# Schematic_1_0.net
KiCad netlist of a schematic drawn in Altium Designer
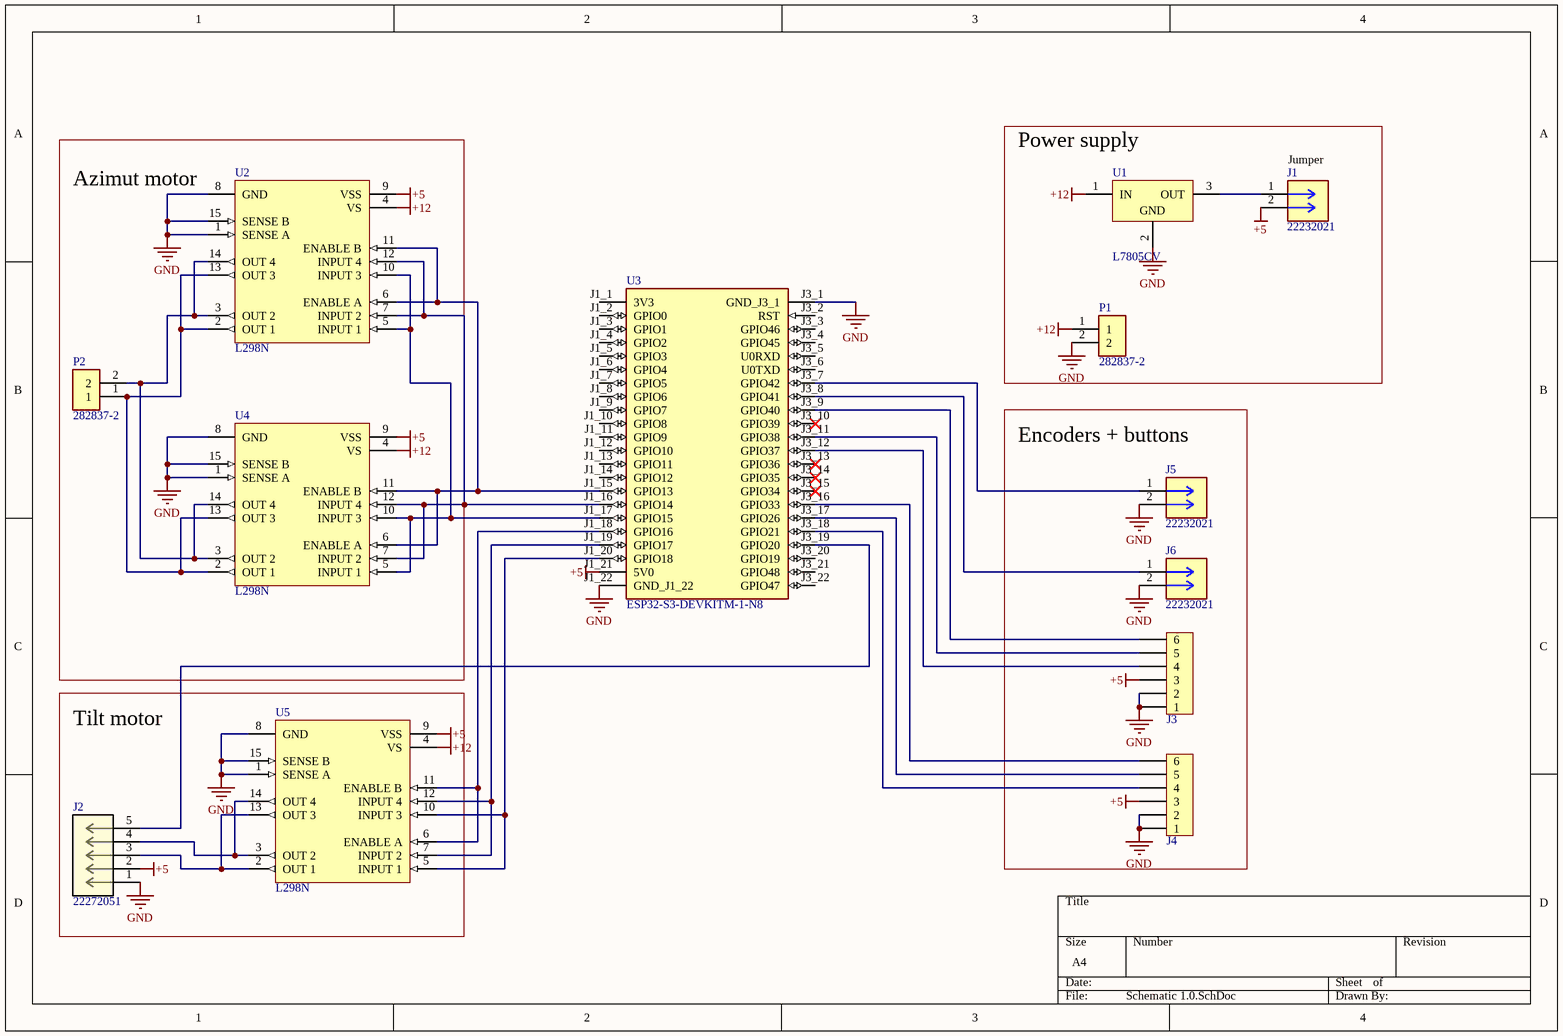
[diagram p0: Schematic 1.0.SchDoc]

(export (version "E")
  (design (tool "Eeschema 10.0.6"))
  (components
    (comp (ref "J1")
      (value "22232021")
      (footprint "CONN_A-6373-02A_MOL")
      (description "Connector Header Through Hole 2 position 0.100 (2.54mm)")
      (fields (field (name "MF") "Molex"))
      (libsource (lib "Emil Beier") (part "22232021"))
    )
    (comp (ref "J2")
      (value "22272051")
      (footprint "CONN_AE-6410-05A_MOL")
      (description "KK 254 Wire-to-Board Header, Vertical, with Friction Lock, 5 Circuits, Tin (Sn) Plating")
      (fields (field (name "COPYRIGHT") "Copyright (C) 2025 Ultra Librarian. All rights reserved."))
      (libsource (lib "22272051 - 5pin molex") (part "22272051"))
    )
    (comp (ref "J3")
      (value "Header 1x6")
      (footprint "Header 1x6")
      (libsource (lib "AAURacing") (part "Header 1x6"))
    )
    (comp (ref "J4")
      (value "Header 1x6")
      (footprint "Header 1x6")
      (libsource (lib "AAURacing") (part "Header 1x6"))
    )
    (comp (ref "J5")
      (value "22232021")
      (footprint "CONN_A-6373-02A_MOL")
      (description "Connector Header Through Hole 2 position 0.100 (2.54mm)")
      (fields (field (name "MF") "Molex"))
      (libsource (lib "Emil Beier") (part "22232021"))
    )
    (comp (ref "J6")
      (value "22232021")
      (footprint "CONN_A-6373-02A_MOL")
      (description "Connector Header Through Hole 2 position 0.100 (2.54mm)")
      (fields (field (name "MF") "Molex"))
      (libsource (lib "Emil Beier") (part "22232021"))
    )
    (comp (ref "P1")
      (value "282837-2")
      (footprint "TE_282837-2")
      (fields (field (name "MF") "TE Connectivity"))
      (libsource (lib "Emil Beier") (part "282837-2"))
    )
    (comp (ref "P2")
      (value "282837-2")
      (footprint "TE_282837-2")
      (fields (field (name "MF") "TE Connectivity"))
      (libsource (lib "") (part "282837-2_1"))
    )
    (comp (ref "U1")
      (value "L7805CV")
      (footprint "TO220")
      (description "Positive Voltage Regulator, 5V, 3-Pin TO-220")
      (libsource (lib "Altium Content Vault") (part "PM-REG-L4940-SIL3"))
    )
    (comp (ref "U2")
      (value "L298N")
      (footprint "STM-FM-15")
      (description "Dual Full-Bridge Driver, 4.8 to 46 V, -40 to 150 degC, 15-Pin FM (MW 15L), RoHS, Tube")
      (fields (field (name "MANUFACTURER") "STMicroelectronics") (field (name "PARTNUMBER") "L298"))
      (libsource (lib "Altium Content Vault") (part "STM-L298-15"))
    )
    (comp (ref "U3")
      (value "ESP32-S3-DEVKITM-1-N8")
      (footprint "MODULE_ESP32-S3-DEVKITM-1-N8")
      (fields (field (name "MF") "{'manufacturer': u'Espressif Systems'}"))
      (libsource (lib "Emil Beier") (part "ESP32-S3-DEVKITM-1-N8"))
    )
    (comp (ref "U4")
      (value "L298N")
      (footprint "STM-FM-15")
      (description "Dual Full-Bridge Driver, 4.8 to 46 V, -40 to 150 degC, 15-Pin FM (MW 15L), RoHS, Tube")
      (fields (field (name "MANUFACTURER") "STMicroelectronics") (field (name "PARTNUMBER") "L298"))
      (libsource (lib "Altium Content Vault") (part "STM-L298-15"))
    )
    (comp (ref "U5")
      (value "L298N")
      (footprint "STM-FM-15")
      (description "Dual Full-Bridge Driver, 4.8 to 46 V, -40 to 150 degC, 15-Pin FM (MW 15L), RoHS, Tube")
      (fields (field (name "MANUFACTURER") "STMicroelectronics") (field (name "PARTNUMBER") "L298"))
      (libsource (lib "Altium Content Vault") (part "STM-L298-15"))
    )
  )
  (nets
    (net (code "1") (name "+5") (class "Default")
      (node (ref "J1") (pin "2") (pinfunction "2_2") (pintype "passive"))
      (node (ref "J2") (pin "2") (pinfunction "2_2") (pintype "passive"))
      (node (ref "J3") (pin "3") (pinfunction "3_3") (pintype "passive"))
      (node (ref "J4") (pin "3") (pinfunction "3_3") (pintype "passive"))
      (node (ref "U2") (pin "9") (pinfunction "VSS_9") (pintype "power_in"))
      (node (ref "U3") (pin "J1_21") (pinfunction "5V0_J1_21") (pintype "power_in"))
      (node (ref "U4") (pin "9") (pinfunction "VSS_9") (pintype "power_in"))
      (node (ref "U5") (pin "9") (pinfunction "VSS_9") (pintype "power_in"))
    )
    (net (code "2") (name "+12") (class "Default")
      (node (ref "P1") (pin "1") (pinfunction "1_1") (pintype "passive"))
      (node (ref "U1") (pin "1") (pinfunction "IN_1") (pintype "power_in"))
      (node (ref "U2") (pin "4") (pinfunction "VS_4") (pintype "power_in"))
      (node (ref "U4") (pin "4") (pinfunction "VS_4") (pintype "power_in"))
      (node (ref "U5") (pin "4") (pinfunction "VS_4") (pintype "power_in"))
    )
    (net (code "3") (name "GND") (class "Default")
      (node (ref "J2") (pin "1") (pinfunction "1_1") (pintype "passive"))
      (node (ref "J3") (pin "1") (pinfunction "1_1") (pintype "passive"))
      (node (ref "J3") (pin "2") (pinfunction "2_2") (pintype "passive"))
      (node (ref "J4") (pin "1") (pinfunction "1_1") (pintype "passive"))
      (node (ref "J4") (pin "2") (pinfunction "2_2") (pintype "passive"))
      (node (ref "J5") (pin "2") (pinfunction "2_2") (pintype "passive"))
      (node (ref "J6") (pin "2") (pinfunction "2_2") (pintype "passive"))
      (node (ref "P1") (pin "2") (pinfunction "2_2") (pintype "passive"))
      (node (ref "U1") (pin "2") (pinfunction "GND_2") (pintype "power_in"))
      (node (ref "U2") (pin "1") (pinfunction "SENSE_A_1") (pintype "input"))
      (node (ref "U2") (pin "15") (pinfunction "SENSE_B_15") (pintype "input"))
      (node (ref "U2") (pin "8") (pinfunction "GND_8") (pintype "power_in"))
      (node (ref "U3") (pin "J1_22") (pinfunction "GND_J1_22_J1_22") (pintype "power_in"))
      (node (ref "U3") (pin "J3_1") (pinfunction "GND_J3_1_J3_1") (pintype "power_in"))
      (node (ref "U4") (pin "1") (pinfunction "SENSE_A_1") (pintype "input"))
      (node (ref "U4") (pin "15") (pinfunction "SENSE_B_15") (pintype "input"))
      (node (ref "U4") (pin "8") (pinfunction "GND_8") (pintype "power_in"))
      (node (ref "U5") (pin "1") (pinfunction "SENSE_A_1") (pintype "input"))
      (node (ref "U5") (pin "15") (pinfunction "SENSE_B_15") (pintype "input"))
      (node (ref "U5") (pin "8") (pinfunction "GND_8") (pintype "power_in"))
    )
    (net (code "4") (name "Net-(U1-OUT)") (class "Default")
      (node (ref "J1") (pin "1") (pinfunction "1_1") (pintype "passive"))
      (node (ref "U1") (pin "3") (pinfunction "OUT_3") (pintype "power_in"))
    )
    (net (code "5") (name "Net-(U2-ENABLE_A)") (class "Default")
      (node (ref "U2") (pin "11") (pinfunction "ENABLE_B_11") (pintype "input"))
      (node (ref "U2") (pin "6") (pinfunction "ENABLE_A_6") (pintype "input"))
      (node (ref "U3") (pin "J1_15") (pinfunction "GPIO13_J1_15") (pintype "bidirectional"))
      (node (ref "U4") (pin "11") (pinfunction "ENABLE_B_11") (pintype "input"))
      (node (ref "U4") (pin "6") (pinfunction "ENABLE_A_6") (pintype "input"))
    )
    (net (code "6") (name "Net-(U2-INPUT_1)") (class "Default")
      (node (ref "U2") (pin "10") (pinfunction "INPUT_3_10") (pintype "input"))
      (node (ref "U2") (pin "5") (pinfunction "INPUT_1_5") (pintype "input"))
      (node (ref "U3") (pin "J1_17") (pinfunction "GPIO15_J1_17") (pintype "bidirectional"))
      (node (ref "U4") (pin "10") (pinfunction "INPUT_3_10") (pintype "input"))
      (node (ref "U4") (pin "5") (pinfunction "INPUT_1_5") (pintype "input"))
    )
    (net (code "7") (name "Net-(U2-INPUT_2)") (class "Default")
      (node (ref "U2") (pin "12") (pinfunction "INPUT_4_12") (pintype "input"))
      (node (ref "U2") (pin "7") (pinfunction "INPUT_2_7") (pintype "input"))
      (node (ref "U3") (pin "J1_16") (pinfunction "GPIO14_J1_16") (pintype "bidirectional"))
      (node (ref "U4") (pin "12") (pinfunction "INPUT_4_12") (pintype "input"))
      (node (ref "U4") (pin "7") (pinfunction "INPUT_2_7") (pintype "input"))
    )
    (net (code "8") (name "Net-(U2-OUT_1)") (class "Default")
      (node (ref "P2") (pin "1") (pinfunction "1_1") (pintype "passive"))
      (node (ref "U2") (pin "13") (pinfunction "OUT_3_13") (pintype "output"))
      (node (ref "U2") (pin "2") (pinfunction "OUT_1_2") (pintype "output"))
      (node (ref "U4") (pin "13") (pinfunction "OUT_3_13") (pintype "output"))
      (node (ref "U4") (pin "2") (pinfunction "OUT_1_2") (pintype "output"))
    )
    (net (code "9") (name "Net-(U2-OUT_2)") (class "Default")
      (node (ref "P2") (pin "2") (pinfunction "2_2") (pintype "passive"))
      (node (ref "U2") (pin "14") (pinfunction "OUT_4_14") (pintype "output"))
      (node (ref "U2") (pin "3") (pinfunction "OUT_2_3") (pintype "output"))
      (node (ref "U4") (pin "14") (pinfunction "OUT_4_14") (pintype "output"))
      (node (ref "U4") (pin "3") (pinfunction "OUT_2_3") (pintype "output"))
    )
    (net (code "10") (name "Net-(U3-GPIO16)") (class "Default")
      (node (ref "U3") (pin "J1_18") (pinfunction "GPIO16_J1_18") (pintype "bidirectional"))
      (node (ref "U5") (pin "11") (pinfunction "ENABLE_B_11") (pintype "input"))
      (node (ref "U5") (pin "6") (pinfunction "ENABLE_A_6") (pintype "input"))
    )
    (net (code "11") (name "Net-(U3-GPIO17)") (class "Default")
      (node (ref "U3") (pin "J1_19") (pinfunction "GPIO17_J1_19") (pintype "bidirectional"))
      (node (ref "U5") (pin "12") (pinfunction "INPUT_4_12") (pintype "input"))
      (node (ref "U5") (pin "7") (pinfunction "INPUT_2_7") (pintype "input"))
    )
    (net (code "12") (name "Net-(U3-GPIO18)") (class "Default")
      (node (ref "U3") (pin "J1_20") (pinfunction "GPIO18_J1_20") (pintype "bidirectional"))
      (node (ref "U5") (pin "10") (pinfunction "INPUT_3_10") (pintype "input"))
      (node (ref "U5") (pin "5") (pinfunction "INPUT_1_5") (pintype "input"))
    )
    (net (code "13") (name "Net-(U3-GPIO20)") (class "Default")
      (node (ref "J2") (pin "5") (pinfunction "5_5") (pintype "passive"))
      (node (ref "U3") (pin "J3_19") (pinfunction "GPIO20_J3_19") (pintype "bidirectional"))
    )
    (net (code "14") (name "Net-(U3-GPIO21)") (class "Default")
      (node (ref "J4") (pin "4") (pinfunction "4_4") (pintype "passive"))
      (node (ref "U3") (pin "J3_18") (pinfunction "GPIO21_J3_18") (pintype "bidirectional"))
    )
    (net (code "15") (name "Net-(U3-GPIO26)") (class "Default")
      (node (ref "J4") (pin "5") (pinfunction "5_5") (pintype "passive"))
      (node (ref "U3") (pin "J3_17") (pinfunction "GPIO26_J3_17") (pintype "bidirectional"))
    )
    (net (code "16") (name "Net-(U3-GPIO33)") (class "Default")
      (node (ref "J4") (pin "6") (pinfunction "6_6") (pintype "passive"))
      (node (ref "U3") (pin "J3_16") (pinfunction "GPIO33_J3_16") (pintype "bidirectional"))
    )
    (net (code "17") (name "Net-(U3-GPIO37)") (class "Default")
      (node (ref "J3") (pin "4") (pinfunction "4_4") (pintype "passive"))
      (node (ref "U3") (pin "J3_12") (pinfunction "GPIO37_J3_12") (pintype "bidirectional"))
    )
    (net (code "18") (name "Net-(U3-GPIO38)") (class "Default")
      (node (ref "J3") (pin "5") (pinfunction "5_5") (pintype "passive"))
      (node (ref "U3") (pin "J3_11") (pinfunction "GPIO38_J3_11") (pintype "bidirectional"))
    )
    (net (code "19") (name "Net-(U3-GPIO40)") (class "Default")
      (node (ref "J3") (pin "6") (pinfunction "6_6") (pintype "passive"))
      (node (ref "U3") (pin "J3_9") (pinfunction "GPIO40_J3_9") (pintype "bidirectional"))
    )
    (net (code "20") (name "Net-(U3-GPIO41)") (class "Default")
      (node (ref "J6") (pin "1") (pinfunction "1_1") (pintype "passive"))
      (node (ref "U3") (pin "J3_8") (pinfunction "GPIO41_J3_8") (pintype "bidirectional"))
    )
    (net (code "21") (name "Net-(U3-GPIO42)") (class "Default")
      (node (ref "J5") (pin "1") (pinfunction "1_1") (pintype "passive"))
      (node (ref "U3") (pin "J3_7") (pinfunction "GPIO42_J3_7") (pintype "bidirectional"))
    )
    (net (code "22") (name "Net-(U5-OUT_1)") (class "Default")
      (node (ref "J2") (pin "3") (pinfunction "3_3") (pintype "passive"))
      (node (ref "U5") (pin "13") (pinfunction "OUT_3_13") (pintype "output"))
      (node (ref "U5") (pin "2") (pinfunction "OUT_1_2") (pintype "output"))
    )
    (net (code "23") (name "Net-(U5-OUT_2)") (class "Default")
      (node (ref "J2") (pin "4") (pinfunction "4_4") (pintype "passive"))
      (node (ref "U5") (pin "14") (pinfunction "OUT_4_14") (pintype "output"))
      (node (ref "U5") (pin "3") (pinfunction "OUT_2_3") (pintype "output"))
    )
    (net (code "24") (name "unconnected-(U3-3V3-PadJ1_1)") (class "Default")
      (node (ref "U3") (pin "J1_1") (pinfunction "3V3_J1_1") (pintype "power_in"))
    )
    (net (code "25") (name "unconnected-(U3-GPIO0-PadJ1_2)") (class "Default")
      (node (ref "U3") (pin "J1_2") (pinfunction "GPIO0_J1_2") (pintype "bidirectional"))
    )
    (net (code "26") (name "unconnected-(U3-GPIO1-PadJ1_3)") (class "Default")
      (node (ref "U3") (pin "J1_3") (pinfunction "GPIO1_J1_3") (pintype "bidirectional"))
    )
    (net (code "27") (name "unconnected-(U3-GPIO2-PadJ1_4)") (class "Default")
      (node (ref "U3") (pin "J1_4") (pinfunction "GPIO2_J1_4") (pintype "bidirectional"))
    )
    (net (code "28") (name "unconnected-(U3-GPIO3-PadJ1_5)") (class "Default")
      (node (ref "U3") (pin "J1_5") (pinfunction "GPIO3_J1_5") (pintype "bidirectional"))
    )
    (net (code "29") (name "unconnected-(U3-GPIO4-PadJ1_6)") (class "Default")
      (node (ref "U3") (pin "J1_6") (pinfunction "GPIO4_J1_6") (pintype "bidirectional"))
    )
    (net (code "30") (name "unconnected-(U3-GPIO5-PadJ1_7)") (class "Default")
      (node (ref "U3") (pin "J1_7") (pinfunction "GPIO5_J1_7") (pintype "bidirectional"))
    )
    (net (code "31") (name "unconnected-(U3-GPIO6-PadJ1_8)") (class "Default")
      (node (ref "U3") (pin "J1_8") (pinfunction "GPIO6_J1_8") (pintype "bidirectional"))
    )
    (net (code "32") (name "unconnected-(U3-GPIO7-PadJ1_9)") (class "Default")
      (node (ref "U3") (pin "J1_9") (pinfunction "GPIO7_J1_9") (pintype "bidirectional"))
    )
    (net (code "33") (name "unconnected-(U3-GPIO8-PadJ1_10)") (class "Default")
      (node (ref "U3") (pin "J1_10") (pinfunction "GPIO8_J1_10") (pintype "bidirectional"))
    )
    (net (code "34") (name "unconnected-(U3-GPIO9-PadJ1_11)") (class "Default")
      (node (ref "U3") (pin "J1_11") (pinfunction "GPIO9_J1_11") (pintype "bidirectional"))
    )
    (net (code "35") (name "unconnected-(U3-GPIO10-PadJ1_12)") (class "Default")
      (node (ref "U3") (pin "J1_12") (pinfunction "GPIO10_J1_12") (pintype "bidirectional"))
    )
    (net (code "36") (name "unconnected-(U3-GPIO11-PadJ1_13)") (class "Default")
      (node (ref "U3") (pin "J1_13") (pinfunction "GPIO11_J1_13") (pintype "bidirectional"))
    )
    (net (code "37") (name "unconnected-(U3-GPIO12-PadJ1_14)") (class "Default")
      (node (ref "U3") (pin "J1_14") (pinfunction "GPIO12_J1_14") (pintype "bidirectional"))
    )
    (net (code "38") (name "unconnected-(U3-GPIO19-PadJ3_20)") (class "Default")
      (node (ref "U3") (pin "J3_20") (pinfunction "GPIO19_J3_20") (pintype "bidirectional"))
    )
    (net (code "39") (name "unconnected-(U3-GPIO34-PadJ3_15)") (class "Default")
      (node (ref "U3") (pin "J3_15") (pinfunction "GPIO34_J3_15") (pintype "bidirectional+no_connect"))
    )
    (net (code "40") (name "unconnected-(U3-GPIO35-PadJ3_14)") (class "Default")
      (node (ref "U3") (pin "J3_14") (pinfunction "GPIO35_J3_14") (pintype "bidirectional+no_connect"))
    )
    (net (code "41") (name "unconnected-(U3-GPIO36-PadJ3_13)") (class "Default")
      (node (ref "U3") (pin "J3_13") (pinfunction "GPIO36_J3_13") (pintype "bidirectional+no_connect"))
    )
    (net (code "42") (name "unconnected-(U3-GPIO39-PadJ3_10)") (class "Default")
      (node (ref "U3") (pin "J3_10") (pinfunction "GPIO39_J3_10") (pintype "bidirectional+no_connect"))
    )
    (net (code "43") (name "unconnected-(U3-GPIO45-PadJ3_4)") (class "Default")
      (node (ref "U3") (pin "J3_4") (pinfunction "GPIO45_J3_4") (pintype "bidirectional"))
    )
    (net (code "44") (name "unconnected-(U3-GPIO46-PadJ3_3)") (class "Default")
      (node (ref "U3") (pin "J3_3") (pinfunction "GPIO46_J3_3") (pintype "bidirectional"))
    )
    (net (code "45") (name "unconnected-(U3-GPIO47-PadJ3_22)") (class "Default")
      (node (ref "U3") (pin "J3_22") (pinfunction "GPIO47_J3_22") (pintype "bidirectional"))
    )
    (net (code "46") (name "unconnected-(U3-GPIO48-PadJ3_21)") (class "Default")
      (node (ref "U3") (pin "J3_21") (pinfunction "GPIO48_J3_21") (pintype "bidirectional"))
    )
    (net (code "47") (name "unconnected-(U3-RST-PadJ3_2)") (class "Default")
      (node (ref "U3") (pin "J3_2") (pinfunction "RST_J3_2") (pintype "input"))
    )
    (net (code "48") (name "unconnected-(U3-U0RXD-PadJ3_5)") (class "Default")
      (node (ref "U3") (pin "J3_5") (pinfunction "U0RXD_J3_5") (pintype "bidirectional"))
    )
    (net (code "49") (name "unconnected-(U3-U0TXD-PadJ3_6)") (class "Default")
      (node (ref "U3") (pin "J3_6") (pinfunction "U0TXD_J3_6") (pintype "bidirectional"))
    )
  )
)
